# v2_0.net
KiCad netlist of a schematic drawn in Altium Designer
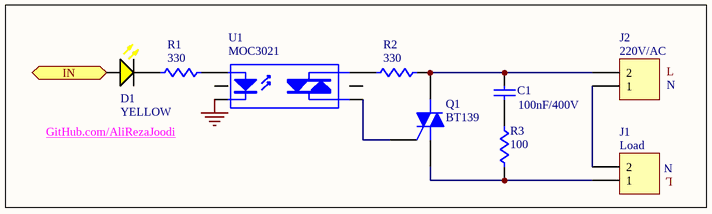
[diagram p0: v2.0.SchDoc]

(export (version "E")
  (design (tool "Eeschema 10.0.6"))
  (components
    (comp (ref "C1")
      (value "100nF/400V")
      (footprint "CAPR7.62-6.8x5")
      (description "Capacitor")
      (fields (field (name "MANUFACTURER") "Generic Components") (field (name "PUBLISHER") "Altium Limited"))
      (libsource (lib "Miscellaneous Devices") (part "Cap"))
    )
    (comp (ref "D1")
      (value "YELLOW")
      (footprint "LED_THD_5MM_YELLOW")
      (description "LED, Yellow")
      (fields (field (name "MANUFACTURER") "Generic Components") (field (name "PUBLISHER") "Altium Limited"))
      (libsource (lib "Display") (part "LED_YELLOW"))
    )
    (comp (ref "J1")
      (value "2PIN")
      (footprint "Fonics_2PIN_1")
      (description "Header, 2-Pin")
      (fields (field (name "PUBLISHER") "Altium Limited"))
      (libsource (lib "Miscellaneous Connectors") (part "Header 2"))
    )
    (comp (ref "J2")
      (value "2PIN")
      (footprint "Fonics_2PIN_1")
      (description "Header, 2-Pin")
      (fields (field (name "PUBLISHER") "Altium Limited"))
      (libsource (lib "Miscellaneous Connectors") (part "Header 2"))
    )
    (comp (ref "Q1")
      (value "BT139")
      (footprint "TO220V")
      (description "Silicon Bidirectional Triode Thyristor")
      (fields (field (name "MANUFACTURER") "Generic Components") (field (name "PUBLISHER") "Altium Limited"))
      (libsource (lib "Miscellaneous Devices") (part "Triac"))
    )
    (comp (ref "R1")
      (value "330")
      (footprint "AXIAL-0.4")
      (description "Resistor")
      (fields (field (name "MANUFACTURER") "Generic Components") (field (name "PUBLISHER") "Altium Limited"))
      (libsource (lib "Miscellaneous Devices") (part "Res1"))
    )
    (comp (ref "R2")
      (value "330")
      (footprint "AXIAL-0.4")
      (description "Resistor")
      (fields (field (name "MANUFACTURER") "Generic Components") (field (name "PUBLISHER") "Altium Limited"))
      (libsource (lib "Miscellaneous Devices") (part "Res1"))
    )
    (comp (ref "R3")
      (value "100")
      (footprint "AXIAL-0.4")
      (description "Resistor")
      (fields (field (name "MANUFACTURER") "Generic Components") (field (name "PUBLISHER") "Altium Limited"))
      (libsource (lib "Miscellaneous Devices") (part "Res1"))
    )
    (comp (ref "U1")
      (value "MOC3021")
      (footprint "DIP-6")
      (description "Opto-Triac")
      (fields
        (field (name "PUBLISHER") "www.picpars.com")
        (field (name "DESIGNER") "Seyed Mohsen Ghasemian")
        (field (name "E-MAIL") "picpars@gmail.com")
      )
      (libsource (lib "PicPars.com_usefully_Library") (part "MOC3021-3"))
    )
  )
  (nets
    (net (code "1") (name "/IN") (class "Default")
      (node (ref "D1") (pin "1") (pinfunction "A_1") (pintype "passive"))
    )
    (net (code "2") (name "GND") (class "Default")
      (node (ref "U1") (pin "2") (pinfunction "K_2") (pintype "passive"))
    )
    (net (code "3") (name "Net-(C1-Pad1)") (class "Default")
      (node (ref "C1") (pin "1") (pinfunction "1_1") (pintype "passive"))
      (node (ref "R3") (pin "2") (pinfunction "2_2") (pintype "passive"))
    )
    (net (code "4") (name "Net-(D1-K)") (class "Default")
      (node (ref "D1") (pin "2") (pinfunction "K_2") (pintype "passive"))
      (node (ref "R1") (pin "1") (pinfunction "1_1") (pintype "passive"))
    )
    (net (code "5") (name "Net-(J1-Pad2)") (class "Default")
      (node (ref "J1") (pin "2") (pinfunction "2_2") (pintype "passive"))
      (node (ref "J2") (pin "1") (pinfunction "1_1") (pintype "passive"))
    )
    (net (code "6") (name "Net-(Q1-G)") (class "Default")
      (node (ref "Q1") (pin "3") (pinfunction "G_3") (pintype "passive"))
      (node (ref "U1") (pin "6") (pinfunction "A/K_6") (pintype "passive"))
    )
    (net (code "7") (name "Net-(Q1-M1)") (class "Default")
      (node (ref "J1") (pin "1") (pinfunction "1_1") (pintype "passive"))
      (node (ref "Q1") (pin "1") (pinfunction "M1_1") (pintype "passive"))
      (node (ref "R3") (pin "1") (pinfunction "1_1") (pintype "passive"))
    )
    (net (code "8") (name "Net-(Q1-M2)") (class "Default")
      (node (ref "C1") (pin "2") (pinfunction "2_2") (pintype "passive"))
      (node (ref "J2") (pin "2") (pinfunction "2_2") (pintype "passive"))
      (node (ref "Q1") (pin "2") (pinfunction "M2_2") (pintype "passive"))
      (node (ref "R2") (pin "2") (pinfunction "2_2") (pintype "passive"))
    )
    (net (code "9") (name "Net-(R2-Pad1)") (class "Default")
      (node (ref "R2") (pin "1") (pinfunction "1_1") (pintype "passive"))
      (node (ref "U1") (pin "4") (pinfunction "A/K_4") (pintype "passive"))
    )
    (net (code "10") (name "Net-(U1-A)") (class "Default")
      (node (ref "R1") (pin "2") (pinfunction "2_2") (pintype "passive"))
      (node (ref "U1") (pin "1") (pinfunction "A_1") (pintype "passive"))
    )
    (net (code "11") (name "unconnected-(U1-NC-Pad3)") (class "Default")
      (node (ref "U1") (pin "3") (pinfunction "NC_3") (pintype "passive"))
    )
    (net (code "12") (name "unconnected-(U1-NC-Pad5)") (class "Default")
      (node (ref "U1") (pin "5") (pinfunction "NC_5") (pintype "passive"))
    )
  )
)
